# atmega_midi_pg800.net
KiCad netlist of a schematic drawn in EAGLE
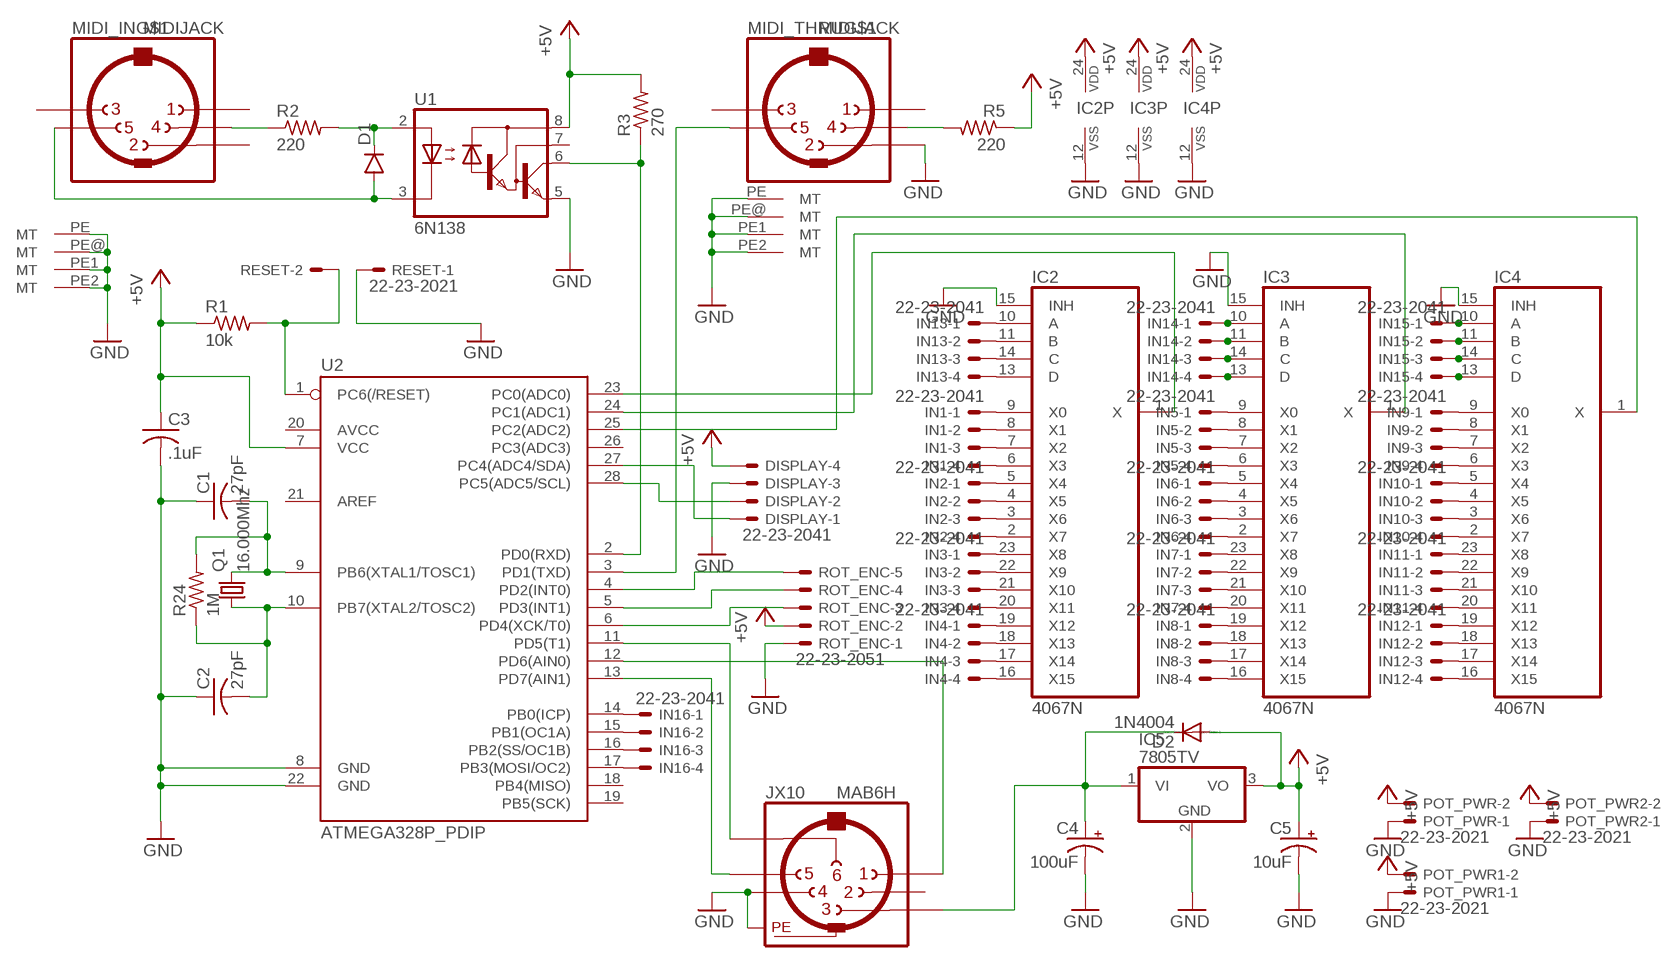
[diagram p0: schematic, sheet 1]

(export (version "E")
  (design (tool "Eeschema 10.0.6"))
  (components
    (comp (ref "C1")
      (value "27pF")
      (footprint "eagle-import:C025-040X050")
      (libsource (lib "eagle-import") (part "C-US025-040X050"))
    )
    (comp (ref "C2")
      (value "27pF")
      (footprint "eagle-import:C025-040X050")
      (libsource (lib "eagle-import") (part "C-US025-040X050"))
    )
    (comp (ref "C3")
      (value ".1uF")
      (footprint "eagle-import:C025-030X050")
      (libsource (lib "eagle-import") (part "C-US025-030X050"))
    )
    (comp (ref "C4")
      (value "100uF")
      (footprint "eagle-import:B45181A")
      (libsource (lib "eagle-import") (part "CPOL-USB45181A"))
    )
    (comp (ref "C5")
      (value "10uF")
      (footprint "eagle-import:B45181A")
      (libsource (lib "eagle-import") (part "CPOL-USB45181A"))
    )
    (comp (ref "D1")
      (value "DIODE1N4148")
      (footprint "eagle-import:DIODE-1N4148")
      (libsource (lib "eagle-import") (part "DIODE1N4148"))
    )
    (comp (ref "D2")
      (value "1N4004")
      (footprint "eagle-import:DO41-10")
      (libsource (lib "eagle-import") (part "1N4004"))
    )
    (comp (ref "DISPLAY")
      (value "22-23-2041")
      (footprint "eagle-import:22-23-2041")
      (fields (field (name "MF") "MOLEX"))
      (libsource (lib "eagle-import") (part "22-23-2041"))
    )
    (comp (ref "IC2")
      (value "4067N")
      (footprint "eagle-import:DIL24-6")
      (libsource (lib "eagle-import") (part "4067N"))
    )
    (comp (ref "IC3")
      (value "4067N")
      (footprint "eagle-import:DIL24-6")
      (libsource (lib "eagle-import") (part "4067N"))
    )
    (comp (ref "IC4")
      (value "4067N")
      (footprint "eagle-import:DIL24-6")
      (libsource (lib "eagle-import") (part "4067N"))
    )
    (comp (ref "IC5")
      (value "7805TV")
      (footprint "eagle-import:TO220V")
      (libsource (lib "eagle-import") (part "78TV05"))
    )
    (comp (ref "IN1")
      (value "22-23-2041")
      (footprint "eagle-import:22-23-2041")
      (fields (field (name "MF") "MOLEX"))
      (libsource (lib "eagle-import") (part "22-23-2041"))
    )
    (comp (ref "IN2")
      (value "22-23-2041")
      (footprint "eagle-import:22-23-2041")
      (fields (field (name "MF") "MOLEX"))
      (libsource (lib "eagle-import") (part "22-23-2041"))
    )
    (comp (ref "IN3")
      (value "22-23-2041")
      (footprint "eagle-import:22-23-2041")
      (fields (field (name "MF") "MOLEX"))
      (libsource (lib "eagle-import") (part "22-23-2041"))
    )
    (comp (ref "IN4")
      (value "22-23-2041")
      (footprint "eagle-import:22-23-2041")
      (fields (field (name "MF") "MOLEX"))
      (libsource (lib "eagle-import") (part "22-23-2041"))
    )
    (comp (ref "IN5")
      (value "22-23-2041")
      (footprint "eagle-import:22-23-2041")
      (fields (field (name "MF") "MOLEX"))
      (libsource (lib "eagle-import") (part "22-23-2041"))
    )
    (comp (ref "IN6")
      (value "22-23-2041")
      (footprint "eagle-import:22-23-2041")
      (fields (field (name "MF") "MOLEX"))
      (libsource (lib "eagle-import") (part "22-23-2041"))
    )
    (comp (ref "IN7")
      (value "22-23-2041")
      (footprint "eagle-import:22-23-2041")
      (fields (field (name "MF") "MOLEX"))
      (libsource (lib "eagle-import") (part "22-23-2041"))
    )
    (comp (ref "IN8")
      (value "22-23-2041")
      (footprint "eagle-import:22-23-2041")
      (fields (field (name "MF") "MOLEX"))
      (libsource (lib "eagle-import") (part "22-23-2041"))
    )
    (comp (ref "IN9")
      (value "22-23-2041")
      (footprint "eagle-import:22-23-2041")
      (fields (field (name "MF") "MOLEX"))
      (libsource (lib "eagle-import") (part "22-23-2041"))
    )
    (comp (ref "IN10")
      (value "22-23-2041")
      (footprint "eagle-import:22-23-2041")
      (fields (field (name "MF") "MOLEX"))
      (libsource (lib "eagle-import") (part "22-23-2041"))
    )
    (comp (ref "IN11")
      (value "22-23-2041")
      (footprint "eagle-import:22-23-2041")
      (fields (field (name "MF") "MOLEX"))
      (libsource (lib "eagle-import") (part "22-23-2041"))
    )
    (comp (ref "IN12")
      (value "22-23-2041")
      (footprint "eagle-import:22-23-2041")
      (fields (field (name "MF") "MOLEX"))
      (libsource (lib "eagle-import") (part "22-23-2041"))
    )
    (comp (ref "IN13")
      (value "22-23-2041")
      (footprint "eagle-import:22-23-2041")
      (fields (field (name "MF") "MOLEX"))
      (libsource (lib "eagle-import") (part "22-23-2041"))
    )
    (comp (ref "IN14")
      (value "22-23-2041")
      (footprint "eagle-import:22-23-2041")
      (fields (field (name "MF") "MOLEX"))
      (libsource (lib "eagle-import") (part "22-23-2041"))
    )
    (comp (ref "IN15")
      (value "22-23-2041")
      (footprint "eagle-import:22-23-2041")
      (fields (field (name "MF") "MOLEX"))
      (libsource (lib "eagle-import") (part "22-23-2041"))
    )
    (comp (ref "IN16")
      (value "22-23-2041")
      (footprint "eagle-import:22-23-2041")
      (fields (field (name "MF") "MOLEX"))
      (libsource (lib "eagle-import") (part "22-23-2041"))
    )
    (comp (ref "JX10")
      (value "MAB6H")
      (footprint "eagle-import:MAB6H")
      (fields (field (name "MF") "FARNELL") (field (name "MPN") "MAB 6 H"))
      (libsource (lib "eagle-import") (part "MAB6H"))
    )
    (comp (ref "MIDI_IN")
      (value "MIDIJACK")
      (footprint "eagle-import:CP-2350")
      (libsource (lib "eagle-import") (part "MIDIJACK"))
    )
    (comp (ref "MIDI_THRU")
      (value "MIDIJACK")
      (footprint "eagle-import:CP-2350")
      (libsource (lib "eagle-import") (part "MIDIJACK"))
    )
    (comp (ref "POT_PWR")
      (value "22-23-2021")
      (footprint "eagle-import:22-23-2021")
      (fields (field (name "MF") "MOLEX"))
      (libsource (lib "eagle-import") (part "22-23-2021"))
    )
    (comp (ref "POT_PWR1")
      (value "22-23-2021")
      (footprint "eagle-import:22-23-2021")
      (fields (field (name "MF") "MOLEX"))
      (libsource (lib "eagle-import") (part "22-23-2021"))
    )
    (comp (ref "POT_PWR2")
      (value "22-23-2021")
      (footprint "eagle-import:22-23-2021")
      (fields (field (name "MF") "MOLEX"))
      (libsource (lib "eagle-import") (part "22-23-2021"))
    )
    (comp (ref "Q1")
      (value "16.000Mhz")
      (footprint "eagle-import:HC49_S")
      (libsource (lib "eagle-import") (part "CRYSTALHC49S"))
    )
    (comp (ref "R1")
      (value "10k")
      (footprint "eagle-import:0207_7")
      (libsource (lib "eagle-import") (part "R-US_0207/7"))
    )
    (comp (ref "R2")
      (value "220")
      (footprint "eagle-import:0207_7")
      (libsource (lib "eagle-import") (part "R-US_0207/7"))
    )
    (comp (ref "R3")
      (value "270")
      (footprint "eagle-import:0207_7")
      (libsource (lib "eagle-import") (part "R-US_0207/7"))
    )
    (comp (ref "R5")
      (value "220")
      (footprint "eagle-import:0309_10")
      (libsource (lib "eagle-import") (part "R-US_0309/10"))
    )
    (comp (ref "R24")
      (value "1M")
      (footprint "eagle-import:0207_7")
      (libsource (lib "eagle-import") (part "R-US_0207/7"))
    )
    (comp (ref "RESET")
      (value "22-23-2021")
      (footprint "eagle-import:22-23-2021")
      (fields (field (name "MF") "MOLEX"))
      (libsource (lib "eagle-import") (part "22-23-2021"))
    )
    (comp (ref "ROT_ENC")
      (value "22-23-2051")
      (footprint "eagle-import:22-23-2051")
      (fields (field (name "MF") "MOLEX"))
      (libsource (lib "eagle-import") (part "22-23-2051"))
    )
    (comp (ref "U1")
      (value "6N138")
      (footprint "eagle-import:DIL08")
      (fields (field (name "MF") "VISHAY/TELEFUNKEN"))
      (libsource (lib "eagle-import") (part "6N138"))
    )
    (comp (ref "U2")
      (value "ATMEGA328P_PDIP")
      (footprint "eagle-import:DIL28-3")
      (libsource (lib "eagle-import") (part "ATMEGA328P_PDIP"))
    )
  )
  (nets
    (net (code "1") (name "+5V") (class "Default")
      (node (ref "C3") (pin "1") (pinfunction "1_1") (pintype "passive"))
      (node (ref "C5") (pin "+") (pinfunction "+_+") (pintype "passive"))
      (node (ref "D2") (pin "A") (pinfunction "A_A") (pintype "passive"))
      (node (ref "DISPLAY") (pin "4") (pinfunction "S_4") (pintype "passive"))
      (node (ref "IC2") (pin "24") (pinfunction "VDD_24") (pintype "power_in"))
      (node (ref "IC3") (pin "24") (pinfunction "VDD_24") (pintype "power_in"))
      (node (ref "IC4") (pin "24") (pinfunction "VDD_24") (pintype "power_in"))
      (node (ref "IC5") (pin "3") (pinfunction "VO_3") (pintype "passive"))
      (node (ref "POT_PWR") (pin "2") (pinfunction "S_2") (pintype "passive"))
      (node (ref "POT_PWR1") (pin "2") (pinfunction "S_2") (pintype "passive"))
      (node (ref "POT_PWR2") (pin "2") (pinfunction "S_2") (pintype "passive"))
      (node (ref "R1") (pin "1") (pinfunction "1_1") (pintype "passive"))
      (node (ref "R3") (pin "2") (pinfunction "2_2") (pintype "passive"))
      (node (ref "R5") (pin "1") (pinfunction "1_1") (pintype "passive"))
      (node (ref "ROT_ENC") (pin "2") (pinfunction "S_2") (pintype "passive"))
      (node (ref "U1") (pin "8") (pinfunction "VCC_8") (pintype "passive"))
      (node (ref "U2") (pin "7") (pinfunction "VCC_7") (pintype "bidirectional"))
    )
    (net (code "2") (name "GND") (class "Default")
      (node (ref "C1") (pin "1") (pinfunction "1_1") (pintype "passive"))
      (node (ref "C2") (pin "1") (pinfunction "1_1") (pintype "passive"))
      (node (ref "C3") (pin "2") (pinfunction "2_2") (pintype "passive"))
      (node (ref "C4") (pin "-") (pinfunction "-_-") (pintype "passive"))
      (node (ref "C5") (pin "-") (pinfunction "-_-") (pintype "passive"))
      (node (ref "DISPLAY") (pin "3") (pinfunction "S_3") (pintype "passive"))
      (node (ref "IC2") (pin "12") (pinfunction "VSS_12") (pintype "power_in"))
      (node (ref "IC2") (pin "15") (pinfunction "INH_15") (pintype "input"))
      (node (ref "IC3") (pin "12") (pinfunction "VSS_12") (pintype "power_in"))
      (node (ref "IC3") (pin "15") (pinfunction "INH_15") (pintype "input"))
      (node (ref "IC4") (pin "12") (pinfunction "VSS_12") (pintype "power_in"))
      (node (ref "IC4") (pin "15") (pinfunction "INH_15") (pintype "input"))
      (node (ref "IC5") (pin "2") (pinfunction "GND_2") (pintype "passive"))
      (node (ref "JX10") (pin "4") (pinfunction "4_4") (pintype "passive"))
      (node (ref "JX10") (pin "PE") (pinfunction "PE_PE") (pintype "power_in"))
      (node (ref "JX10") (pin "PE@") (pinfunction "PE_PE@") (pintype "power_in"))
      (node (ref "MIDI_IN") (pin "PE") (pinfunction "MT_PE") (pintype "passive"))
      (node (ref "MIDI_IN") (pin "PE1") (pinfunction "MT_PE1") (pintype "passive"))
      (node (ref "MIDI_IN") (pin "PE2") (pinfunction "MT_PE2") (pintype "passive"))
      (node (ref "MIDI_IN") (pin "PE@") (pinfunction "MT_PE@") (pintype "passive"))
      (node (ref "MIDI_THRU") (pin "2") (pinfunction "2_2") (pintype "passive"))
      (node (ref "MIDI_THRU") (pin "PE") (pinfunction "MT_PE") (pintype "passive"))
      (node (ref "MIDI_THRU") (pin "PE1") (pinfunction "MT_PE1") (pintype "passive"))
      (node (ref "MIDI_THRU") (pin "PE2") (pinfunction "MT_PE2") (pintype "passive"))
      (node (ref "MIDI_THRU") (pin "PE@") (pinfunction "MT_PE@") (pintype "passive"))
      (node (ref "POT_PWR") (pin "1") (pinfunction "S_1") (pintype "passive"))
      (node (ref "POT_PWR1") (pin "1") (pinfunction "S_1") (pintype "passive"))
      (node (ref "POT_PWR2") (pin "1") (pinfunction "S_1") (pintype "passive"))
      (node (ref "RESET") (pin "1") (pinfunction "S_1") (pintype "passive"))
      (node (ref "ROT_ENC") (pin "1") (pinfunction "S_1") (pintype "passive"))
      (node (ref "U1") (pin "5") (pinfunction "GND_5") (pintype "passive"))
      (node (ref "U2") (pin "22") (pinfunction "GND_22") (pintype "bidirectional"))
      (node (ref "U2") (pin "8") (pinfunction "GND_8") (pintype "bidirectional"))
    )
    (net (code "3") (name "Net-(DISPLAYA-S)") (class "Default")
      (node (ref "DISPLAY") (pin "1") (pinfunction "S_1") (pintype "passive"))
      (node (ref "U2") (pin "27") (pinfunction "PC4(ADC4/SDA)_27") (pintype "bidirectional"))
    )
    (net (code "4") (name "Net-(DISPLAYB-S)") (class "Default")
      (node (ref "DISPLAY") (pin "2") (pinfunction "S_2") (pintype "passive"))
      (node (ref "U2") (pin "28") (pinfunction "PC5(ADC5/SCL)_28") (pintype "bidirectional"))
    )
    (net (code "5") (name "Net-(IC2A-A)") (class "Default")
      (node (ref "IC2") (pin "10") (pinfunction "A_10") (pintype "input"))
      (node (ref "IN13") (pin "1") (pinfunction "S_1") (pintype "passive"))
    )
    (net (code "6") (name "Net-(IC2A-B)") (class "Default")
      (node (ref "IC2") (pin "11") (pinfunction "B_11") (pintype "input"))
      (node (ref "IN13") (pin "2") (pinfunction "S_2") (pintype "passive"))
    )
    (net (code "7") (name "Net-(IC2A-C)") (class "Default")
      (node (ref "IC2") (pin "14") (pinfunction "C_14") (pintype "input"))
      (node (ref "IN13") (pin "3") (pinfunction "S_3") (pintype "passive"))
    )
    (net (code "8") (name "Net-(IC2A-D)") (class "Default")
      (node (ref "IC2") (pin "13") (pinfunction "D_13") (pintype "input"))
      (node (ref "IN13") (pin "4") (pinfunction "S_4") (pintype "passive"))
    )
    (net (code "9") (name "Net-(IC2A-X)") (class "Default")
      (node (ref "IC2") (pin "1") (pinfunction "X_1") (pintype "output"))
      (node (ref "U2") (pin "23") (pinfunction "PC0(ADC0)_23") (pintype "bidirectional"))
    )
    (net (code "10") (name "Net-(IC2A-X0)") (class "Default")
      (node (ref "IC2") (pin "9") (pinfunction "X0_9") (pintype "input"))
      (node (ref "IN1") (pin "1") (pinfunction "S_1") (pintype "passive"))
    )
    (net (code "11") (name "Net-(IC2A-X1)") (class "Default")
      (node (ref "IC2") (pin "8") (pinfunction "X1_8") (pintype "input"))
      (node (ref "IN1") (pin "2") (pinfunction "S_2") (pintype "passive"))
    )
    (net (code "12") (name "Net-(IC2A-X2)") (class "Default")
      (node (ref "IC2") (pin "7") (pinfunction "X2_7") (pintype "input"))
      (node (ref "IN1") (pin "3") (pinfunction "S_3") (pintype "passive"))
    )
    (net (code "13") (name "Net-(IC2A-X3)") (class "Default")
      (node (ref "IC2") (pin "6") (pinfunction "X3_6") (pintype "input"))
      (node (ref "IN1") (pin "4") (pinfunction "S_4") (pintype "passive"))
    )
    (net (code "14") (name "Net-(IC2A-X4)") (class "Default")
      (node (ref "IC2") (pin "5") (pinfunction "X4_5") (pintype "input"))
      (node (ref "IN2") (pin "1") (pinfunction "S_1") (pintype "passive"))
    )
    (net (code "15") (name "Net-(IC2A-X5)") (class "Default")
      (node (ref "IC2") (pin "4") (pinfunction "X5_4") (pintype "input"))
      (node (ref "IN2") (pin "2") (pinfunction "S_2") (pintype "passive"))
    )
    (net (code "16") (name "Net-(IC2A-X6)") (class "Default")
      (node (ref "IC2") (pin "3") (pinfunction "X6_3") (pintype "input"))
      (node (ref "IN2") (pin "3") (pinfunction "S_3") (pintype "passive"))
    )
    (net (code "17") (name "Net-(IC2A-X7)") (class "Default")
      (node (ref "IC2") (pin "2") (pinfunction "X7_2") (pintype "input"))
      (node (ref "IN2") (pin "4") (pinfunction "S_4") (pintype "passive"))
    )
    (net (code "18") (name "Net-(IC2A-X8)") (class "Default")
      (node (ref "IC2") (pin "23") (pinfunction "X8_23") (pintype "input"))
      (node (ref "IN3") (pin "1") (pinfunction "S_1") (pintype "passive"))
    )
    (net (code "19") (name "Net-(IC2A-X9)") (class "Default")
      (node (ref "IC2") (pin "22") (pinfunction "X9_22") (pintype "input"))
      (node (ref "IN3") (pin "2") (pinfunction "S_2") (pintype "passive"))
    )
    (net (code "20") (name "Net-(IC2A-X10)") (class "Default")
      (node (ref "IC2") (pin "21") (pinfunction "X10_21") (pintype "input"))
      (node (ref "IN3") (pin "3") (pinfunction "S_3") (pintype "passive"))
    )
    (net (code "21") (name "Net-(IC2A-X11)") (class "Default")
      (node (ref "IC2") (pin "20") (pinfunction "X11_20") (pintype "input"))
      (node (ref "IN3") (pin "4") (pinfunction "S_4") (pintype "passive"))
    )
    (net (code "22") (name "Net-(IC2A-X12)") (class "Default")
      (node (ref "IC2") (pin "19") (pinfunction "X12_19") (pintype "input"))
      (node (ref "IN4") (pin "1") (pinfunction "S_1") (pintype "passive"))
    )
    (net (code "23") (name "Net-(IC2A-X13)") (class "Default")
      (node (ref "IC2") (pin "18") (pinfunction "X13_18") (pintype "input"))
      (node (ref "IN4") (pin "2") (pinfunction "S_2") (pintype "passive"))
    )
    (net (code "24") (name "Net-(IC2A-X14)") (class "Default")
      (node (ref "IC2") (pin "17") (pinfunction "X14_17") (pintype "input"))
      (node (ref "IN4") (pin "3") (pinfunction "S_3") (pintype "passive"))
    )
    (net (code "25") (name "Net-(IC2A-X15)") (class "Default")
      (node (ref "IC2") (pin "16") (pinfunction "X15_16") (pintype "input"))
      (node (ref "IN4") (pin "4") (pinfunction "S_4") (pintype "passive"))
    )
    (net (code "26") (name "Net-(IC3A-A)") (class "Default")
      (node (ref "IC3") (pin "10") (pinfunction "A_10") (pintype "input"))
      (node (ref "IN14") (pin "1") (pinfunction "S_1") (pintype "passive"))
    )
    (net (code "27") (name "Net-(IC3A-B)") (class "Default")
      (node (ref "IC3") (pin "11") (pinfunction "B_11") (pintype "input"))
      (node (ref "IN14") (pin "2") (pinfunction "S_2") (pintype "passive"))
    )
    (net (code "28") (name "Net-(IC3A-C)") (class "Default")
      (node (ref "IC3") (pin "14") (pinfunction "C_14") (pintype "input"))
      (node (ref "IN14") (pin "3") (pinfunction "S_3") (pintype "passive"))
    )
    (net (code "29") (name "Net-(IC3A-D)") (class "Default")
      (node (ref "IC3") (pin "13") (pinfunction "D_13") (pintype "input"))
      (node (ref "IN14") (pin "4") (pinfunction "S_4") (pintype "passive"))
    )
    (net (code "30") (name "Net-(IC3A-X)") (class "Default")
      (node (ref "IC3") (pin "1") (pinfunction "X_1") (pintype "output"))
      (node (ref "U2") (pin "24") (pinfunction "PC1(ADC1)_24") (pintype "bidirectional"))
    )
    (net (code "31") (name "Net-(IC3A-X0)") (class "Default")
      (node (ref "IC3") (pin "9") (pinfunction "X0_9") (pintype "input"))
      (node (ref "IN5") (pin "1") (pinfunction "S_1") (pintype "passive"))
    )
    (net (code "32") (name "Net-(IC3A-X1)") (class "Default")
      (node (ref "IC3") (pin "8") (pinfunction "X1_8") (pintype "input"))
      (node (ref "IN5") (pin "2") (pinfunction "S_2") (pintype "passive"))
    )
    (net (code "33") (name "Net-(IC3A-X2)") (class "Default")
      (node (ref "IC3") (pin "7") (pinfunction "X2_7") (pintype "input"))
      (node (ref "IN5") (pin "3") (pinfunction "S_3") (pintype "passive"))
    )
    (net (code "34") (name "Net-(IC3A-X3)") (class "Default")
      (node (ref "IC3") (pin "6") (pinfunction "X3_6") (pintype "input"))
      (node (ref "IN5") (pin "4") (pinfunction "S_4") (pintype "passive"))
    )
    (net (code "35") (name "Net-(IC3A-X4)") (class "Default")
      (node (ref "IC3") (pin "5") (pinfunction "X4_5") (pintype "input"))
      (node (ref "IN6") (pin "1") (pinfunction "S_1") (pintype "passive"))
    )
    (net (code "36") (name "Net-(IC3A-X5)") (class "Default")
      (node (ref "IC3") (pin "4") (pinfunction "X5_4") (pintype "input"))
      (node (ref "IN6") (pin "2") (pinfunction "S_2") (pintype "passive"))
    )
    (net (code "37") (name "Net-(IC3A-X6)") (class "Default")
      (node (ref "IC3") (pin "3") (pinfunction "X6_3") (pintype "input"))
      (node (ref "IN6") (pin "3") (pinfunction "S_3") (pintype "passive"))
    )
    (net (code "38") (name "Net-(IC3A-X7)") (class "Default")
      (node (ref "IC3") (pin "2") (pinfunction "X7_2") (pintype "input"))
      (node (ref "IN6") (pin "4") (pinfunction "S_4") (pintype "passive"))
    )
    (net (code "39") (name "Net-(IC3A-X8)") (class "Default")
      (node (ref "IC3") (pin "23") (pinfunction "X8_23") (pintype "input"))
      (node (ref "IN7") (pin "1") (pinfunction "S_1") (pintype "passive"))
    )
    (net (code "40") (name "Net-(IC3A-X9)") (class "Default")
      (node (ref "IC3") (pin "22") (pinfunction "X9_22") (pintype "input"))
      (node (ref "IN7") (pin "2") (pinfunction "S_2") (pintype "passive"))
    )
    (net (code "41") (name "Net-(IC3A-X10)") (class "Default")
      (node (ref "IC3") (pin "21") (pinfunction "X10_21") (pintype "input"))
      (node (ref "IN7") (pin "3") (pinfunction "S_3") (pintype "passive"))
    )
    (net (code "42") (name "Net-(IC3A-X11)") (class "Default")
      (node (ref "IC3") (pin "20") (pinfunction "X11_20") (pintype "input"))
      (node (ref "IN7") (pin "4") (pinfunction "S_4") (pintype "passive"))
    )
    (net (code "43") (name "Net-(IC3A-X12)") (class "Default")
      (node (ref "IC3") (pin "19") (pinfunction "X12_19") (pintype "input"))
      (node (ref "IN8") (pin "1") (pinfunction "S_1") (pintype "passive"))
    )
    (net (code "44") (name "Net-(IC3A-X13)") (class "Default")
      (node (ref "IC3") (pin "18") (pinfunction "X13_18") (pintype "input"))
      (node (ref "IN8") (pin "2") (pinfunction "S_2") (pintype "passive"))
    )
    (net (code "45") (name "Net-(IC3A-X14)") (class "Default")
      (node (ref "IC3") (pin "17") (pinfunction "X14_17") (pintype "input"))
      (node (ref "IN8") (pin "3") (pinfunction "S_3") (pintype "passive"))
    )
    (net (code "46") (name "Net-(IC3A-X15)") (class "Default")
      (node (ref "IC3") (pin "16") (pinfunction "X15_16") (pintype "input"))
      (node (ref "IN8") (pin "4") (pinfunction "S_4") (pintype "passive"))
    )
    (net (code "47") (name "Net-(IC4A-A)") (class "Default")
      (node (ref "IC4") (pin "10") (pinfunction "A_10") (pintype "input"))
      (node (ref "IN15") (pin "1") (pinfunction "S_1") (pintype "passive"))
    )
    (net (code "48") (name "Net-(IC4A-B)") (class "Default")
      (node (ref "IC4") (pin "11") (pinfunction "B_11") (pintype "input"))
      (node (ref "IN15") (pin "2") (pinfunction "S_2") (pintype "passive"))
    )
    (net (code "49") (name "Net-(IC4A-C)") (class "Default")
      (node (ref "IC4") (pin "14") (pinfunction "C_14") (pintype "input"))
      (node (ref "IN15") (pin "3") (pinfunction "S_3") (pintype "passive"))
    )
    (net (code "50") (name "Net-(IC4A-D)") (class "Default")
      (node (ref "IC4") (pin "13") (pinfunction "D_13") (pintype "input"))
      (node (ref "IN15") (pin "4") (pinfunction "S_4") (pintype "passive"))
    )
    (net (code "51") (name "Net-(IC4A-X)") (class "Default")
      (node (ref "IC4") (pin "1") (pinfunction "X_1") (pintype "output"))
      (node (ref "U2") (pin "25") (pinfunction "PC2(ADC2)_25") (pintype "bidirectional"))
    )
    (net (code "52") (name "Net-(IC4A-X0)") (class "Default")
      (node (ref "IC4") (pin "9") (pinfunction "X0_9") (pintype "input"))
      (node (ref "IN9") (pin "1") (pinfunction "S_1") (pintype "passive"))
    )
    (net (code "53") (name "Net-(IC4A-X1)") (class "Default")
      (node (ref "IC4") (pin "8") (pinfunction "X1_8") (pintype "input"))
      (node (ref "IN9") (pin "2") (pinfunction "S_2") (pintype "passive"))
    )
    (net (code "54") (name "Net-(IC4A-X2)") (class "Default")
      (node (ref "IC4") (pin "7") (pinfunction "X2_7") (pintype "input"))
      (node (ref "IN9") (pin "3") (pinfunction "S_3") (pintype "passive"))
    )
    (net (code "55") (name "Net-(IC4A-X3)") (class "Default")
      (node (ref "IC4") (pin "6") (pinfunction "X3_6") (pintype "input"))
      (node (ref "IN9") (pin "4") (pinfunction "S_4") (pintype "passive"))
    )
    (net (code "56") (name "Net-(IC4A-X4)") (class "Default")
      (node (ref "IC4") (pin "5") (pinfunction "X4_5") (pintype "input"))
      (node (ref "IN10") (pin "1") (pinfunction "S_1") (pintype "passive"))
    )
    (net (code "57") (name "Net-(IC4A-X5)") (class "Default")
      (node (ref "IC4") (pin "4") (pinfunction "X5_4") (pintype "input"))
      (node (ref "IN10") (pin "2") (pinfunction "S_2") (pintype "passive"))
    )
    (net (code "58") (name "Net-(IC4A-X6)") (class "Default")
      (node (ref "IC4") (pin "3") (pinfunction "X6_3") (pintype "input"))
      (node (ref "IN10") (pin "3") (pinfunction "S_3") (pintype "passive"))
    )
    (net (code "59") (name "Net-(IC4A-X7)") (class "Default")
      (node (ref "IC4") (pin "2") (pinfunction "X7_2") (pintype "input"))
      (node (ref "IN10") (pin "4") (pinfunction "S_4") (pintype "passive"))
    )
    (net (code "60") (name "Net-(IC4A-X8)") (class "Default")
      (node (ref "IC4") (pin "23") (pinfunction "X8_23") (pintype "input"))
      (node (ref "IN11") (pin "1") (pinfunction "S_1") (pintype "passive"))
    )
    (net (code "61") (name "Net-(IC4A-X9)") (class "Default")
      (node (ref "IC4") (pin "22") (pinfunction "X9_22") (pintype "input"))
      (node (ref "IN11") (pin "2") (pinfunction "S_2") (pintype "passive"))
    )
    (net (code "62") (name "Net-(IC4A-X10)") (class "Default")
      (node (ref "IC4") (pin "21") (pinfunction "X10_21") (pintype "input"))
      (node (ref "IN11") (pin "3") (pinfunction "S_3") (pintype "passive"))
    )
    (net (code "63") (name "Net-(IC4A-X11)") (class "Default")
      (node (ref "IC4") (pin "20") (pinfunction "X11_20") (pintype "input"))
      (node (ref "IN11") (pin "4") (pinfunction "S_4") (pintype "passive"))
    )
    (net (code "64") (name "Net-(IC4A-X12)") (class "Default")
      (node (ref "IC4") (pin "19") (pinfunction "X12_19") (pintype "input"))
      (node (ref "IN12") (pin "1") (pinfunction "S_1") (pintype "passive"))
    )
    (net (code "65") (name "Net-(IC4A-X13)") (class "Default")
      (node (ref "IC4") (pin "18") (pinfunction "X13_18") (pintype "input"))
      (node (ref "IN12") (pin "2") (pinfunction "S_2") (pintype "passive"))
    )
    (net (code "66") (name "Net-(IC4A-X14)") (class "Default")
      (node (ref "IC4") (pin "17") (pinfunction "X14_17") (pintype "input"))
      (node (ref "IN12") (pin "3") (pinfunction "S_3") (pintype "passive"))
    )
    (net (code "67") (name "Net-(IC4A-X15)") (class "Default")
      (node (ref "IC4") (pin "16") (pinfunction "X15_16") (pintype "input"))
      (node (ref "IN12") (pin "4") (pinfunction "S_4") (pintype "passive"))
    )
    (net (code "68") (name "Net-(IC5-VI)") (class "Default")
      (node (ref "C4") (pin "+") (pinfunction "+_+") (pintype "passive"))
      (node (ref "D2") (pin "C") (pinfunction "C_C") (pintype "passive"))
      (node (ref "IC5") (pin "1") (pinfunction "VI_1") (pintype "input"))
      (node (ref "JX10") (pin "3") (pinfunction "3_3") (pintype "passive"))
    )
    (net (code "69") (name "Net-(IN16A-S)") (class "Default")
      (node (ref "IN16") (pin "1") (pinfunction "S_1") (pintype "passive"))
      (node (ref "U2") (pin "14") (pinfunction "PB0(ICP)_14") (pintype "bidirectional"))
    )
    (net (code "70") (name "Net-(IN16B-S)") (class "Default")
      (node (ref "IN16") (pin "2") (pinfunction "S_2") (pintype "passive"))
      (node (ref "U2") (pin "15") (pinfunction "PB1(OC1A)_15") (pintype "bidirectional"))
    )
    (net (code "71") (name "Net-(IN16C-S)") (class "Default")
      (node (ref "IN16") (pin "3") (pinfunction "S_3") (pintype "passive"))
      (node (ref "U2") (pin "16") (pinfunction "PB2(SS/OC1B)_16") (pintype "bidirectional"))
    )
    (net (code "72") (name "Net-(IN16D-S)") (class "Default")
      (node (ref "IN16") (pin "4") (pinfunction "S_4") (pintype "passive"))
      (node (ref "U2") (pin "17") (pinfunction "PB3(MOSI/OC2)_17") (pintype "bidirectional"))
    )
    (net (code "73") (name "Net-(MIDI_IN-Pad4)") (class "Default")
      (node (ref "MIDI_IN") (pin "4") (pinfunction "4_4") (pintype "passive"))
      (node (ref "R2") (pin "1") (pinfunction "1_1") (pintype "passive"))
    )
    (net (code "74") (name "Net-(MIDI_THRU-Pad4)") (class "Default")
      (node (ref "MIDI_THRU") (pin "4") (pinfunction "4_4") (pintype "passive"))
      (node (ref "R5") (pin "2") (pinfunction "2_2") (pintype "passive"))
    )
    (net (code "75") (name "Net-(RESETB-S)") (class "Default")
      (node (ref "R1") (pin "2") (pinfunction "2_2") (pintype "passive"))
      (node (ref "RESET") (pin "2") (pinfunction "S_2") (pintype "passive"))
      (node (ref "U2") (pin "1") (pinfunction "PC6(/RESET)_1") (pintype "bidirectional"))
    )
    (net (code "76") (name "Net-(ROT_ENCC-S)") (class "Default")
      (node (ref "ROT_ENC") (pin "3") (pinfunction "S_3") (pintype "passive"))
      (node (ref "U2") (pin "6") (pinfunction "PD4(XCK/T0)_6") (pintype "bidirectional"))
    )
    (net (code "77") (name "Net-(ROT_ENCD-S)") (class "Default")
      (node (ref "ROT_ENC") (pin "4") (pinfunction "S_4") (pintype "passive"))
      (node (ref "U2") (pin "5") (pinfunction "PD3(INT1)_5") (pintype "bidirectional"))
    )
    (net (code "78") (name "Net-(ROT_ENCE-S)") (class "Default")
      (node (ref "ROT_ENC") (pin "5") (pinfunction "S_5") (pintype "passive"))
      (node (ref "U2") (pin "4") (pinfunction "PD2(INT0)_4") (pintype "bidirectional"))
    )
    (net (code "79") (name "Net-(U1-A)") (class "Default")
      (node (ref "D1") (pin "C") (pinfunction "C_C") (pintype "passive"))
      (node (ref "R2") (pin "2") (pinfunction "2_2") (pintype "passive"))
      (node (ref "U1") (pin "2") (pinfunction "A_2") (pintype "passive"))
    )
    (net (code "80") (name "Net-(U1-C)") (class "Default")
      (node (ref "D1") (pin "A") (pinfunction "A_A") (pintype "passive"))
      (node (ref "MIDI_IN") (pin "5") (pinfunction "5_5") (pintype "passive"))
      (node (ref "U1") (pin "3") (pinfunction "C_3") (pintype "passive"))
    )
    (net (code "81") (name "Net-(U1-VO)") (class "Default")
      (node (ref "R3") (pin "1") (pinfunction "1_1") (pintype "passive"))
      (node (ref "U1") (pin "6") (pinfunction "VO_6") (pintype "passive"))
      (node (ref "U2") (pin "2") (pinfunction "PD0(RXD)_2") (pintype "bidirectional"))
    )
    (net (code "82") (name "Net-(U2-PB6(XTAL1{slash}TOSC1))") (class "Default")
      (node (ref "C1") (pin "2") (pinfunction "2_2") (pintype "passive"))
      (node (ref "Q1") (pin "2") (pinfunction "2_2") (pintype "passive"))
      (node (ref "R24") (pin "2") (pinfunction "2_2") (pintype "passive"))
      (node (ref "U2") (pin "9") (pinfunction "PB6(XTAL1/TOSC1)_9") (pintype "bidirectional"))
    )
    (net (code "83") (name "Net-(U2-PB7(XTAL2{slash}TOSC2))") (class "Default")
      (node (ref "C2") (pin "2") (pinfunction "2_2") (pintype "passive"))
      (node (ref "Q1") (pin "1") (pinfunction "1_1") (pintype "passive"))
      (node (ref "R24") (pin "1") (pinfunction "1_1") (pintype "passive"))
      (node (ref "U2") (pin "10") (pinfunction "PB7(XTAL2/TOSC2)_10") (pintype "bidirectional"))
    )
    (net (code "84") (name "Net-(U2-PD1(TXD))") (class "Default")
      (node (ref "MIDI_THRU") (pin "5") (pinfunction "5_5") (pintype "passive"))
      (node (ref "U2") (pin "3") (pinfunction "PD1(TXD)_3") (pintype "bidirectional"))
    )
    (net (code "85") (name "Net-(U2-PD5(T1))") (class "Default")
      (node (ref "JX10") (pin "6") (pinfunction "6_6") (pintype "passive"))
      (node (ref "U2") (pin "11") (pinfunction "PD5(T1)_11") (pintype "bidirectional"))
    )
    (net (code "86") (name "Net-(U2-PD6(AIN0))") (class "Default")
      (node (ref "JX10") (pin "1") (pinfunction "1_1") (pintype "passive"))
      (node (ref "U2") (pin "12") (pinfunction "PD6(AIN0)_12") (pintype "bidirectional"))
    )
    (net (code "87") (name "Net-(U2-PD7(AIN1))") (class "Default")
      (node (ref "JX10") (pin "5") (pinfunction "5_5") (pintype "passive"))
      (node (ref "U2") (pin "13") (pinfunction "PD7(AIN1)_13") (pintype "bidirectional"))
    )
    (net (code "88") (name "unconnected-(JX10-Pad2)") (class "Default")
      (node (ref "JX10") (pin "2") (pinfunction "2_2") (pintype "passive"))
    )
    (net (code "89") (name "unconnected-(MIDI_IN-Pad1)") (class "Default")
      (node (ref "MIDI_IN") (pin "1") (pinfunction "1_1") (pintype "passive"))
    )
    (net (code "90") (name "unconnected-(MIDI_IN-Pad2)") (class "Default")
      (node (ref "MIDI_IN") (pin "2") (pinfunction "2_2") (pintype "passive"))
    )
    (net (code "91") (name "unconnected-(MIDI_IN-Pad3)") (class "Default")
      (node (ref "MIDI_IN") (pin "3") (pinfunction "3_3") (pintype "passive"))
    )
    (net (code "92") (name "unconnected-(MIDI_THRU-Pad1)") (class "Default")
      (node (ref "MIDI_THRU") (pin "1") (pinfunction "1_1") (pintype "passive"))
    )
    (net (code "93") (name "unconnected-(MIDI_THRU-Pad3)") (class "Default")
      (node (ref "MIDI_THRU") (pin "3") (pinfunction "3_3") (pintype "passive"))
    )
    (net (code "94") (name "unconnected-(U1-VB-Pad7)") (class "Default")
      (node (ref "U1") (pin "7") (pinfunction "VB_7") (pintype "passive"))
    )
    (net (code "95") (name "unconnected-(U2-AREF-Pad21)") (class "Default")
      (node (ref "U2") (pin "21") (pinfunction "AREF_21") (pintype "bidirectional"))
    )
    (net (code "96") (name "unconnected-(U2-AVCC-Pad20)") (class "Default")
      (node (ref "U2") (pin "20") (pinfunction "AVCC_20") (pintype "bidirectional"))
    )
    (net (code "97") (name "unconnected-(U2-PB4(MISO)-Pad18)") (class "Default")
      (node (ref "U2") (pin "18") (pinfunction "PB4(MISO)_18") (pintype "bidirectional"))
    )
    (net (code "98") (name "unconnected-(U2-PB5(SCK)-Pad19)") (class "Default")
      (node (ref "U2") (pin "19") (pinfunction "PB5(SCK)_19") (pintype "bidirectional"))
    )
    (net (code "99") (name "unconnected-(U2-PC3(ADC3)-Pad26)") (class "Default")
      (node (ref "U2") (pin "26") (pinfunction "PC3(ADC3)_26") (pintype "bidirectional"))
    )
  )
)
